# Main_Board_-_Single_v20.net
KiCad netlist of a schematic drawn in EAGLE
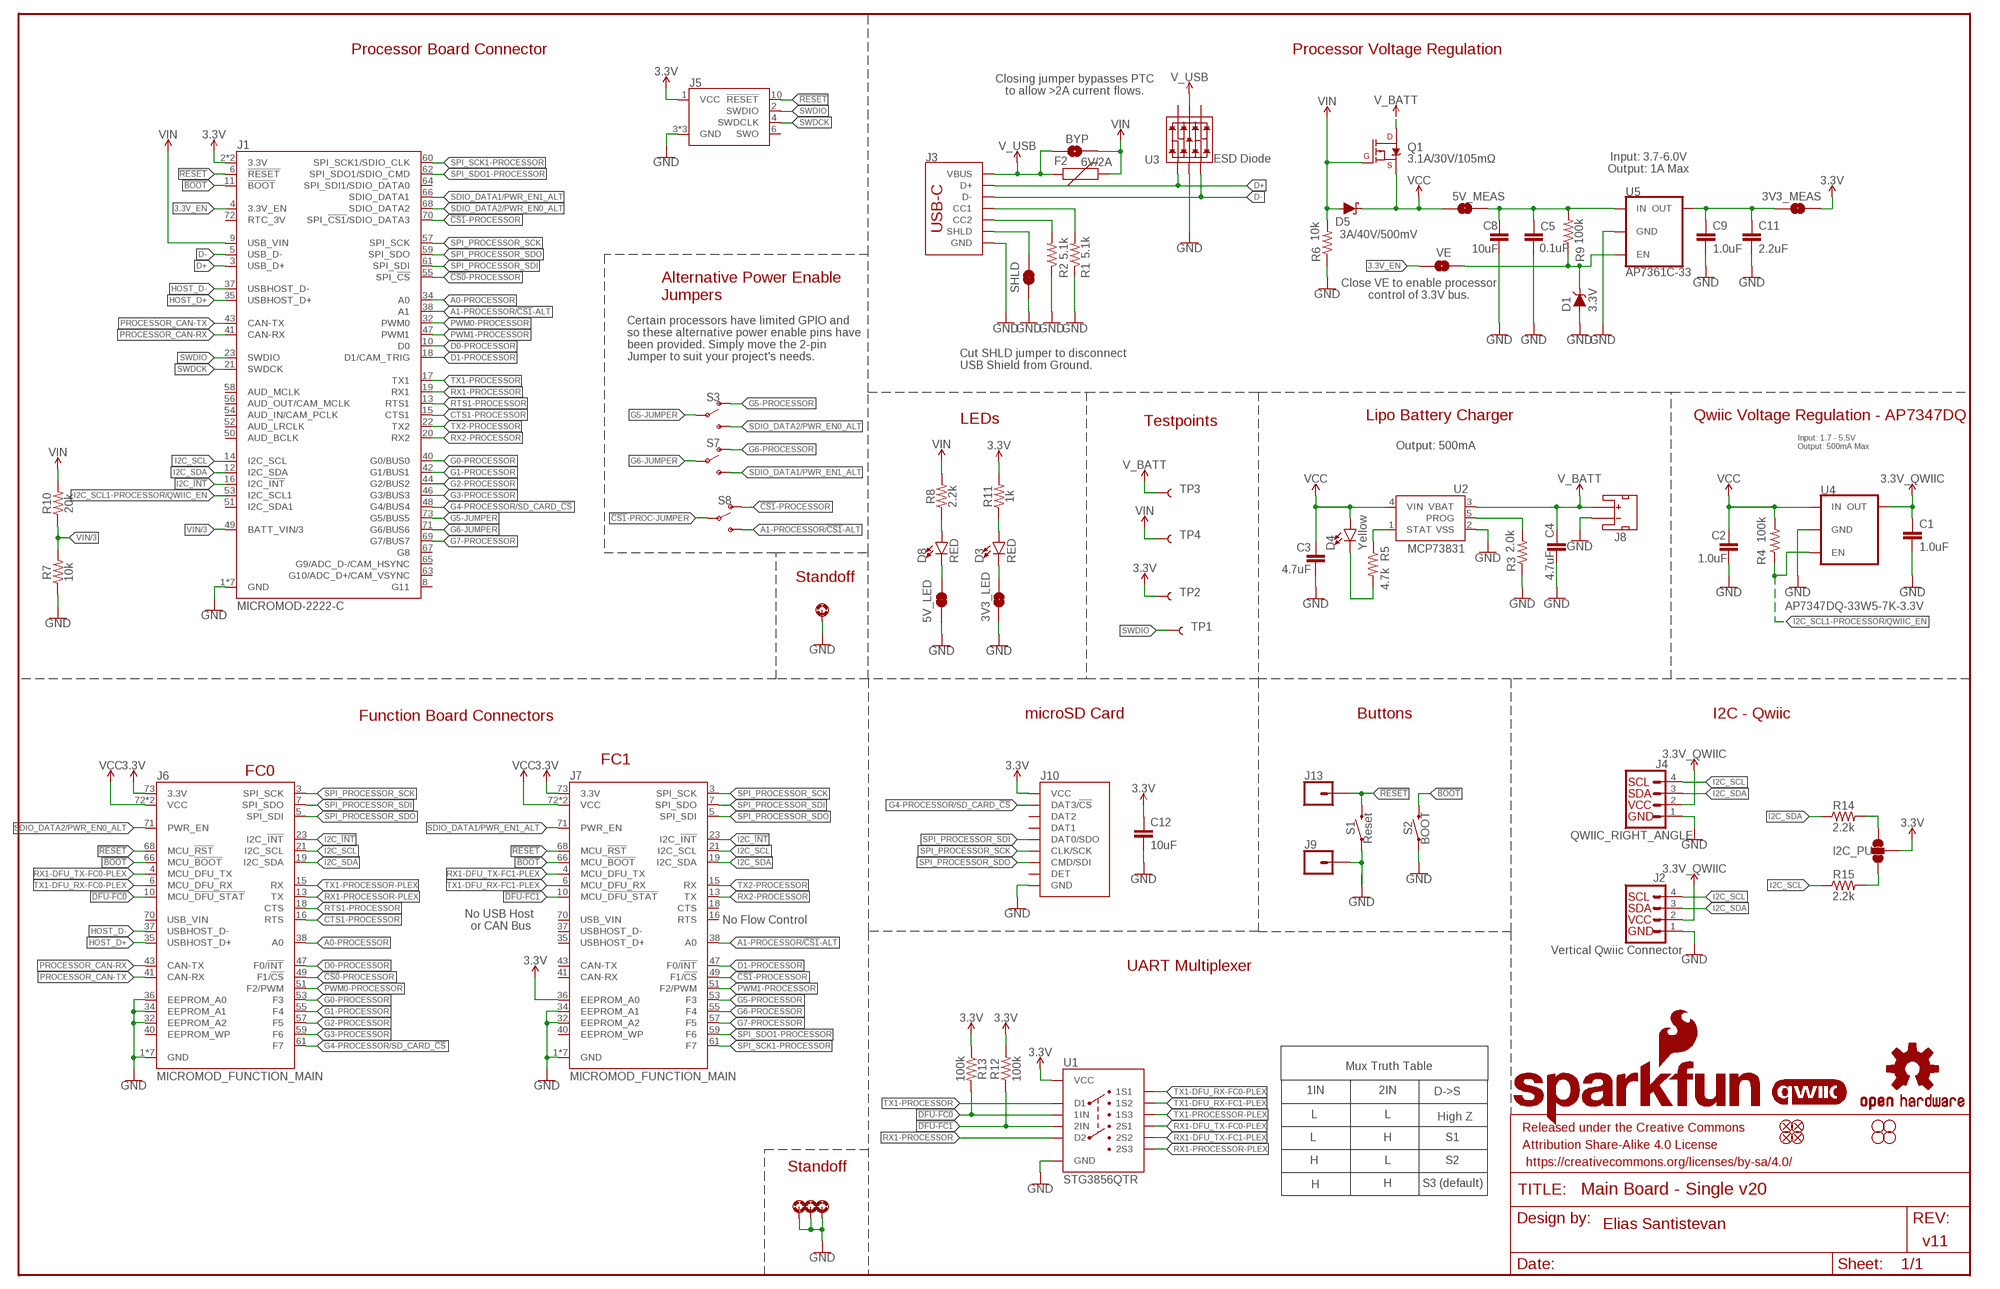
[diagram p0: schematic, sheet 1]

(export (version "E")
  (design (tool "Eeschema 10.0.6"))
  (components
    (comp (ref "3V3_LED")
      (value "JUMPER-SMT_2_NC_TRACE_SILK")
      (footprint "eagle-import:SMT-JUMPER_2_NC_TRACE_SILK")
      (libsource (lib "eagle-import") (part "JUMPER-SMT_2_NC_TRACE_SILK"))
    )
    (comp (ref "3V3_MEAS")
      (value "JUMPER-COMBO_2_NC_TRACE")
      (footprint "eagle-import:COMBO-JUMPER_2_NC_TRACE")
      (libsource (lib "eagle-import") (part "JUMPER-COMBO_2_NC_TRACE"))
    )
    (comp (ref "5V_LED")
      (value "JUMPER-SMT_2_NC_TRACE_SILK")
      (footprint "eagle-import:SMT-JUMPER_2_NC_TRACE_SILK")
      (libsource (lib "eagle-import") (part "JUMPER-SMT_2_NC_TRACE_SILK"))
    )
    (comp (ref "5V_MEAS")
      (value "JUMPER-COMBO_2_NC_TRACE")
      (footprint "eagle-import:COMBO-JUMPER_2_NC_TRACE")
      (libsource (lib "eagle-import") (part "JUMPER-COMBO_2_NC_TRACE"))
    )
    (comp (ref "BYP")
      (value "JUMPER-SMT_2_NO_SILK")
      (footprint "eagle-import:SMT-JUMPER_2_NO_SILK")
      (libsource (lib "eagle-import") (part "JUMPER-SMT_2_NO_SILK"))
    )
    (comp (ref "C1")
      (value "1.0uF")
      (footprint "eagle-import:0603")
      (libsource (lib "eagle-import") (part "1.0UF-0603-16V-10%"))
    )
    (comp (ref "C2")
      (value "1.0uF")
      (footprint "eagle-import:0603")
      (libsource (lib "eagle-import") (part "1.0UF-0603-16V-10%"))
    )
    (comp (ref "C3")
      (value "4.7uF")
      (footprint "eagle-import:0603")
      (libsource (lib "eagle-import") (part "4.7UF-0603-6.3V-(10%)"))
    )
    (comp (ref "C4")
      (value "4.7uF")
      (footprint "eagle-import:0603")
      (libsource (lib "eagle-import") (part "4.7UF-0603-35V-(20%)"))
    )
    (comp (ref "C5")
      (value "0.1uF")
      (footprint "eagle-import:0603")
      (libsource (lib "eagle-import") (part "0.1UF-0603-25V-(+80/-20%)"))
    )
    (comp (ref "C8")
      (value "10uF")
      (footprint "eagle-import:0805")
      (libsource (lib "eagle-import") (part "10UF-0805-10V-10%"))
    )
    (comp (ref "C9")
      (value "1.0uF")
      (footprint "eagle-import:0603")
      (libsource (lib "eagle-import") (part "1.0UF-0603-16V-10%"))
    )
    (comp (ref "C11")
      (value "2.2uF")
      (footprint "eagle-import:0603")
      (libsource (lib "eagle-import") (part "2.2UF-0603-10V-20%"))
    )
    (comp (ref "C12")
      (value "10uF")
      (footprint "eagle-import:0603")
      (libsource (lib "eagle-import") (part "10UF-0603-6.3V-20%"))
    )
    (comp (ref "D1")
      (value "3.3V")
      (footprint "eagle-import:SOD-323")
      (libsource (lib "eagle-import") (part "DIODE-ZENER-MM3Z3V3T1G"))
    )
    (comp (ref "D3")
      (value "RED")
      (footprint "eagle-import:LED-0603")
      (libsource (lib "eagle-import") (part "LED-RED0603"))
    )
    (comp (ref "D4")
      (value "Yellow")
      (footprint "eagle-import:LED-0603")
      (libsource (lib "eagle-import") (part "LED-YELLOW0603"))
    )
    (comp (ref "D5")
      (value "3A/40V/500mV")
      (footprint "eagle-import:SMA-DIODE")
      (libsource (lib "eagle-import") (part "DIODE-SCHOTTKY-B340A"))
    )
    (comp (ref "D8")
      (value "RED")
      (footprint "eagle-import:LED-0603")
      (libsource (lib "eagle-import") (part "LED-RED0603"))
    )
    (comp (ref "F2")
      (value "6V/2A")
      (footprint "eagle-import:1210")
      (libsource (lib "eagle-import") (part "PPTC_6V2A"))
    )
    (comp (ref "FD1")
      (value "FIDUCIAL1X2")
      (footprint "eagle-import:FIDUCIAL-1X2")
      (libsource (lib "eagle-import") (part "FIDUCIAL1X2"))
    )
    (comp (ref "FD2")
      (value "FIDUCIAL1X2")
      (footprint "eagle-import:FIDUCIAL-1X2")
      (libsource (lib "eagle-import") (part "FIDUCIAL1X2"))
    )
    (comp (ref "FD3")
      (value "FIDUCIAL1X2")
      (footprint "eagle-import:FIDUCIAL-1X2")
      (libsource (lib "eagle-import") (part "FIDUCIAL1X2"))
    )
    (comp (ref "FD4")
      (value "FIDUCIAL1X2")
      (footprint "eagle-import:FIDUCIAL-1X2")
      (libsource (lib "eagle-import") (part "FIDUCIAL1X2"))
    )
    (comp (ref "FRAME1")
      (value "FRAME-LEDGER")
      (footprint "eagle-import:CREATIVE_COMMONS")
      (libsource (lib "eagle-import") (part "FRAME-LEDGER"))
    )
    (comp (ref "H2")
      (value "STAND-OFF-REFLOW-M2.5_2.5MM_TALL")
      (footprint "eagle-import:STAND-OFF-REFLOW-M2.5")
      (libsource (lib "eagle-import") (part "STAND-OFF-REFLOW-M2.5_2.5MM_TALL"))
    )
    (comp (ref "H3")
      (value "STAND-OFF-REFLOW-M2.5_2.5MM_TALL")
      (footprint "eagle-import:STAND-OFF-REFLOW-M2.5")
      (libsource (lib "eagle-import") (part "STAND-OFF-REFLOW-M2.5_2.5MM_TALL"))
    )
    (comp (ref "H4")
      (value "STAND-OFF-REFLOW-M2.5_2.5MM_TALL")
      (footprint "eagle-import:STAND-OFF-REFLOW-M2.5")
      (libsource (lib "eagle-import") (part "STAND-OFF-REFLOW-M2.5_2.5MM_TALL"))
    )
    (comp (ref "H8")
      (value "STAND-OFF-REFLOW-M2.5_2.5MM_TALL")
      (footprint "eagle-import:STAND-OFF-REFLOW-M2.5")
      (libsource (lib "eagle-import") (part "STAND-OFF-REFLOW-M2.5_2.5MM_TALL"))
    )
    (comp (ref "H14")
      (value "STAND-OFFTIGHT")
      (footprint "eagle-import:STAND-OFF-TIGHT")
      (libsource (lib "eagle-import") (part "STAND-OFFTIGHT"))
    )
    (comp (ref "H15")
      (value "STAND-OFFTIGHT")
      (footprint "eagle-import:STAND-OFF-TIGHT")
      (libsource (lib "eagle-import") (part "STAND-OFFTIGHT"))
    )
    (comp (ref "H16")
      (value "STAND-OFFTIGHT")
      (footprint "eagle-import:STAND-OFF-TIGHT")
      (libsource (lib "eagle-import") (part "STAND-OFFTIGHT"))
    )
    (comp (ref "H17")
      (value "STAND-OFFTIGHT")
      (footprint "eagle-import:STAND-OFF-TIGHT")
      (libsource (lib "eagle-import") (part "STAND-OFFTIGHT"))
    )
    (comp (ref "I2C_PU")
      (value "JUMPER-SMT_3_2-NC_TRACE_SILK")
      (footprint "eagle-import:SMT-JUMPER_3_2-NC_TRACE_SILK")
      (libsource (lib "eagle-import") (part "JUMPER-SMT_3_2-NC_TRACE_SILK"))
    )
    (comp (ref "J1")
      (value "MICROMOD-2222-C")
      (footprint "eagle-import:M.2-CONNECTOR-E")
      (libsource (lib "eagle-import") (part "MICROMOD-2222-C"))
    )
    (comp (ref "J2")
      (value "Vertical Qwiic Connector")
      (footprint "eagle-import:JST04_1MM_VERT")
      (libsource (lib "eagle-import") (part "QWIIC_CONNECTOR"))
    )
    (comp (ref "J3")
      (value "USB_C_2-LAYER_PADS")
      (footprint "eagle-import:USB-C-16P-2LAYER-PADS")
      (libsource (lib "eagle-import") (part "USB_C_2-LAYER_PADS"))
    )
    (comp (ref "J4")
      (value "QWIIC_RIGHT_ANGLE")
      (footprint "eagle-import:JST04_1MM_RA")
      (libsource (lib "eagle-import") (part "QWIIC_CONNECTORJS-1MM"))
    )
    (comp (ref "J5")
      (value "CORTEX_JTAG_DEBUG_MINIMUM_PTH")
      (footprint "eagle-import:2X5-PTH-1.27MM")
      (libsource (lib "eagle-import") (part "CORTEX_JTAG_DEBUG_MINIMUM_PTH"))
    )
    (comp (ref "J6")
      (value "MICROMOD_FUNCTION_MAIN")
      (footprint "eagle-import:M.2-CONNECTOR-E-FUNCTION-STANDARD")
      (libsource (lib "eagle-import") (part "MICROMOD_FUNCTION_MAIN"))
    )
    (comp (ref "J7")
      (value "MICROMOD_FUNCTION_MAIN")
      (footprint "eagle-import:M.2-CONNECTOR-E-FUNCTION-STANDARD")
      (libsource (lib "eagle-import") (part "MICROMOD_FUNCTION_MAIN"))
    )
    (comp (ref "J8")
      (value "JST_2MM_MALE")
      (footprint "eagle-import:JST-2-SMD")
      (libsource (lib "eagle-import") (part "JST_2MM_MALE"))
    )
    (comp (ref "J9")
      (value "CONN_01PTH_NO_SILK_YES_STOP")
      (footprint "eagle-import:1X01_NO_SILK")
      (libsource (lib "eagle-import") (part "CONN_01PTH_NO_SILK_YES_STOP"))
    )
    (comp (ref "J10")
      (value "MICRO-SD-PUSH-PUSH-EXT-PIN")
      (footprint "eagle-import:MICROSD-EXTERNALPIN")
      (libsource (lib "eagle-import") (part "MICRO-SD-PUSH-PUSH-EXT-PIN"))
    )
    (comp (ref "J13")
      (value "CONN_01PTH_NO_SILK_YES_STOP")
      (footprint "eagle-import:1X01_NO_SILK")
      (libsource (lib "eagle-import") (part "CONN_01PTH_NO_SILK_YES_STOP"))
    )
    (comp (ref "LOGO1")
      (value "QWIIC_LOGO_8MM")
      (footprint "eagle-import:QWIIC_8MM")
      (libsource (lib "eagle-import") (part "QWIIC_LOGO_8MM"))
    )
    (comp (ref "LOGO2")
      (value "SFE_LOGO_NAME_FLAME.3_INCH")
      (footprint "eagle-import:SFE_LOGO_NAME_FLAME_.3")
      (libsource (lib "eagle-import") (part "SFE_LOGO_NAME_FLAME.3_INCH"))
    )
    (comp (ref "LOGO3")
      (value "OSHW-LOGOL")
      (footprint "eagle-import:OSHW-LOGO-L")
      (libsource (lib "eagle-import") (part "OSHW-LOGOL"))
    )
    (comp (ref "Q1")
      (value "3.1A/30V/105mΩ")
      (footprint "eagle-import:SOT23-3")
      (libsource (lib "eagle-import") (part "MOSFET_PCH-DMG2307L"))
    )
    (comp (ref "R1")
      (value "5.1k")
      (footprint "eagle-import:0603")
      (libsource (lib "eagle-import") (part "5.1KOHM5.1KOHM-0603-1/10W-1%"))
    )
    (comp (ref "R2")
      (value "5.1k")
      (footprint "eagle-import:0603")
      (libsource (lib "eagle-import") (part "5.1KOHM5.1KOHM-0603-1/10W-1%"))
    )
    (comp (ref "R3")
      (value "2.0k")
      (footprint "eagle-import:0603")
      (libsource (lib "eagle-import") (part "2.0KOHM-0603-1/10W-5%"))
    )
    (comp (ref "R4")
      (value "100k")
      (footprint "eagle-import:0603")
      (libsource (lib "eagle-import") (part "100KOHM-0603-1/10W-1%"))
    )
    (comp (ref "R5")
      (value "4.7k")
      (footprint "eagle-import:0603")
      (libsource (lib "eagle-import") (part "4.7KOHM-0603-1/10W-1%"))
    )
    (comp (ref "R6")
      (value "10k")
      (footprint "eagle-import:0603")
      (libsource (lib "eagle-import") (part "10KOHM-0603-1/10W-1%"))
    )
    (comp (ref "R7")
      (value "10k")
      (footprint "eagle-import:0603")
      (libsource (lib "eagle-import") (part "10KOHM-0603-1/10W-1%"))
    )
    (comp (ref "R8")
      (value "2.2k")
      (footprint "eagle-import:0603")
      (libsource (lib "eagle-import") (part "2.2KOHM-0603-1/10W-1%"))
    )
    (comp (ref "R9")
      (value "100k")
      (footprint "eagle-import:0603")
      (libsource (lib "eagle-import") (part "100KOHM-0603-1/10W-1%"))
    )
    (comp (ref "R10")
      (value "20k")
      (footprint "eagle-import:0603")
      (libsource (lib "eagle-import") (part "20KOHM-0603-1/10W-1%"))
    )
    (comp (ref "R11")
      (value "1k")
      (footprint "eagle-import:0603")
      (libsource (lib "eagle-import") (part "1KOHM-0603-1/10W-1%"))
    )
    (comp (ref "R12")
      (value "100k")
      (footprint "eagle-import:0603")
      (libsource (lib "eagle-import") (part "100KOHM-0603-1/10W-1%"))
    )
    (comp (ref "R13")
      (value "100k")
      (footprint "eagle-import:0603")
      (libsource (lib "eagle-import") (part "100KOHM-0603-1/10W-1%"))
    )
    (comp (ref "R14")
      (value "2.2k")
      (footprint "eagle-import:0603")
      (libsource (lib "eagle-import") (part "2.2KOHM-0603-1/10W-1%"))
    )
    (comp (ref "R15")
      (value "2.2k")
      (footprint "eagle-import:0603")
      (libsource (lib "eagle-import") (part "2.2KOHM-0603-1/10W-1%"))
    )
    (comp (ref "S1")
      (value "Reset")
      (footprint "eagle-import:TACTILE_SWITCH_SMD_5.2MM")
      (libsource (lib "eagle-import") (part "MOMENTARY-SWITCH-SPST-SMD-5.2-TALL-REDUNDANT"))
    )
    (comp (ref "S2")
      (value "BOOT")
      (footprint "eagle-import:TACTILE_SWITCH_SMD_5.2MM")
      (libsource (lib "eagle-import") (part "MOMENTARY-SWITCH-SPST-SMD-5.2-TALL-REDUNDANT"))
    )
    (comp (ref "S3")
      (value "SWITCH-SPDT-SMD-RIGHT-ANGLE")
      (footprint "eagle-import:SWITCH_SPST_SMD_A")
      (libsource (lib "eagle-import") (part "SWITCH-SPDT-SMD-RIGHT-ANGLE"))
    )
    (comp (ref "S7")
      (value "SWITCH-SPDT-SMD-RIGHT-ANGLE")
      (footprint "eagle-import:SWITCH_SPST_SMD_A")
      (libsource (lib "eagle-import") (part "SWITCH-SPDT-SMD-RIGHT-ANGLE"))
    )
    (comp (ref "S8")
      (value "SWITCH-SPDT-SMD-RIGHT-ANGLE")
      (footprint "eagle-import:SWITCH_SPST_SMD_A")
      (libsource (lib "eagle-import") (part "SWITCH-SPDT-SMD-RIGHT-ANGLE"))
    )
    (comp (ref "SHLD")
      (value "JUMPER-SMT_2_NC_TRACE_SILK")
      (footprint "eagle-import:SMT-JUMPER_2_NC_TRACE_SILK")
      (libsource (lib "eagle-import") (part "JUMPER-SMT_2_NC_TRACE_SILK"))
    )
    (comp (ref "TP1")
      (value "TEST-POINT3X5")
      (footprint "eagle-import:PAD.03X.05")
      (libsource (lib "eagle-import") (part "TEST-POINT3X5"))
    )
    (comp (ref "TP2")
      (value "TEST-POINT3X5")
      (footprint "eagle-import:PAD.03X.05")
      (libsource (lib "eagle-import") (part "TEST-POINT3X5"))
    )
    (comp (ref "TP3")
      (value "TEST-POINT3X5")
      (footprint "eagle-import:PAD.03X.05")
      (libsource (lib "eagle-import") (part "TEST-POINT3X5"))
    )
    (comp (ref "TP4")
      (value "TEST-POINT3X5")
      (footprint "eagle-import:PAD.03X.05")
      (libsource (lib "eagle-import") (part "TEST-POINT3X5"))
    )
    (comp (ref "U1")
      (value "STG3856QTR")
      (footprint "eagle-import:STG3856")
      (libsource (lib "eagle-import") (part "STG3856QTR"))
    )
    (comp (ref "U2")
      (value "MCP73831")
      (footprint "eagle-import:SOT23-5")
      (libsource (lib "eagle-import") (part "MCP73831"))
    )
    (comp (ref "U3")
      (value "ESD Diode")
      (footprint "eagle-import:SOT-23-6")
      (libsource (lib "eagle-import") (part "TVS_DIODE_ARRAYSMD"))
    )
    (comp (ref "U4")
      (value "AP7347DQ-33W5-7K-3.3V")
      (footprint "eagle-import:SOT25")
      (libsource (lib "eagle-import") (part "AP7347DQ-33W5-7K-3.3V"))
    )
    (comp (ref "U5")
      (value "AP7361C-33")
      (footprint "eagle-import:UDFN-8")
      (libsource (lib "eagle-import") (part "AP7361C-33FGEUDFN-8"))
    )
    (comp (ref "VE")
      (value "JUMPER-SMT_2_NO_SILK")
      (footprint "eagle-import:SMT-JUMPER_2_NO_SILK")
      (libsource (lib "eagle-import") (part "JUMPER-SMT_2_NO_SILK"))
    )
  )
  (nets
    (net (code "1") (name "/A1-PROCESSOR{slash}~{CS1}-ALT") (class "Default")
      (node (ref "J1") (pin "38") (pinfunction "A1_38") (pintype "bidirectional"))
      (node (ref "J7") (pin "38") (pinfunction "A0_38") (pintype "bidirectional"))
      (node (ref "S8") (pin "3") (pinfunction "S_3") (pintype "passive"))
    )
    (net (code "2") (name "/G4-PROCESSOR{slash}SD_CARD_~{CS}") (class "Default")
      (node (ref "J1") (pin "48") (pinfunction "G4/BUS4_48") (pintype "bidirectional"))
      (node (ref "J10") (pin "2") (pinfunction "DAT3/~{CS}_2") (pintype "bidirectional"))
      (node (ref "J6") (pin "61") (pinfunction "F7_61") (pintype "bidirectional"))
    )
    (net (code "3") (name "/I2C_~{INT}") (class "Default")
      (node (ref "J1") (pin "16") (pinfunction "I2C_~{INT}_16") (pintype "bidirectional"))
      (node (ref "J6") (pin "23") (pinfunction "I2C_~{INT}_23") (pintype "bidirectional"))
      (node (ref "J7") (pin "23") (pinfunction "I2C_~{INT}_23") (pintype "bidirectional"))
    )
    (net (code "4") (name "/~{BOOT}") (class "Default")
      (node (ref "J1") (pin "11") (pinfunction "~{BOOT}_11") (pintype "bidirectional"))
      (node (ref "J6") (pin "66") (pinfunction "MCU_~{BOOT}_66") (pintype "bidirectional"))
      (node (ref "J7") (pin "66") (pinfunction "MCU_~{BOOT}_66") (pintype "bidirectional"))
      (node (ref "S2") (pin "3") (pinfunction "2_3") (pintype "passive"))
      (node (ref "S2") (pin "4") (pinfunction "2_4") (pintype "passive"))
    )
    (net (code "5") (name "/~{CS0}-PROCESSOR") (class "Default")
      (node (ref "J1") (pin "55") (pinfunction "SPI_~{CS}_55") (pintype "bidirectional"))
      (node (ref "J6") (pin "49") (pinfunction "F1/~{CS}_49") (pintype "bidirectional"))
    )
    (net (code "6") (name "/~{CS1}-PROC-JUMPER") (class "Default")
      (node (ref "S8") (pin "2") (pinfunction "P_2") (pintype "passive"))
    )
    (net (code "7") (name "/~{CS1}-PROCESSOR") (class "Default")
      (node (ref "J1") (pin "70") (pinfunction "SPI_~{CS1}/SDIO_DATA3_70") (pintype "bidirectional"))
      (node (ref "J7") (pin "49") (pinfunction "F1/~{CS}_49") (pintype "bidirectional"))
      (node (ref "S8") (pin "1") (pinfunction "O_1") (pintype "passive"))
    )
    (net (code "8") (name "/~{DFU-FC0}") (class "Default")
      (node (ref "J6") (pin "10") (pinfunction "MCU_~{DFU_STAT}_10") (pintype "bidirectional"))
      (node (ref "R13") (pin "2") (pinfunction "2_2") (pintype "passive"))
      (node (ref "U1") (pin "P12") (pinfunction "1IN_P12") (pintype "bidirectional"))
    )
    (net (code "9") (name "/~{DFU-FC1}") (class "Default")
      (node (ref "J7") (pin "10") (pinfunction "MCU_~{DFU_STAT}_10") (pintype "bidirectional"))
      (node (ref "R12") (pin "1") (pinfunction "1_1") (pintype "passive"))
      (node (ref "U1") (pin "P10") (pinfunction "2IN_P10") (pintype "bidirectional"))
    )
    (net (code "10") (name "/~{RESET}") (class "Default")
      (node (ref "J1") (pin "6") (pinfunction "~{RESET}_6") (pintype "bidirectional"))
      (node (ref "J13") (pin "1") (pinfunction "1_1") (pintype "passive"))
      (node (ref "J5") (pin "10") (pinfunction "~{RESET}_10") (pintype "bidirectional"))
      (node (ref "J6") (pin "68") (pinfunction "MCU_~{RST}_68") (pintype "bidirectional"))
      (node (ref "J7") (pin "68") (pinfunction "MCU_~{RST}_68") (pintype "bidirectional"))
      (node (ref "S1") (pin "3") (pinfunction "2_3") (pintype "passive"))
      (node (ref "S1") (pin "4") (pinfunction "2_4") (pintype "passive"))
    )
    (net (code "11") (name "3.3V") (class "Default")
      (node (ref "3V3_MEAS") (pin "2") (pinfunction "2_2") (pintype "passive"))
      (node (ref "3V3_MEAS") (pin "4") (pinfunction "2_4") (pintype "passive"))
      (node (ref "C12") (pin "1") (pinfunction "1_1") (pintype "passive"))
      (node (ref "I2C_PU") (pin "2") (pinfunction "2_2") (pintype "passive"))
      (node (ref "J1") (pin "2") (pinfunction "3.3V_2") (pintype "bidirectional"))
      (node (ref "J1") (pin "74") (pinfunction "3.3V_74") (pintype "bidirectional"))
      (node (ref "J10") (pin "4") (pinfunction "VCC_4") (pintype "bidirectional"))
      (node (ref "J5") (pin "1") (pinfunction "VCC_1") (pintype "bidirectional"))
      (node (ref "J6") (pin "73") (pinfunction "3.3V_73") (pintype "bidirectional"))
      (node (ref "J7") (pin "36") (pinfunction "EEPROM_A0_36") (pintype "bidirectional"))
      (node (ref "J7") (pin "73") (pinfunction "3.3V_73") (pintype "bidirectional"))
      (node (ref "R11") (pin "2") (pinfunction "2_2") (pintype "passive"))
      (node (ref "R12") (pin "2") (pinfunction "2_2") (pintype "passive"))
      (node (ref "R13") (pin "1") (pinfunction "1_1") (pintype "passive"))
      (node (ref "TP2") (pin "1") (pinfunction "1_1") (pintype "bidirectional"))
      (node (ref "U1") (pin "P11") (pinfunction "VCC_P11") (pintype "power_in"))
    )
    (net (code "12") (name "3.3V_EN") (class "Default")
      (node (ref "J1") (pin "4") (pinfunction "3.3V_EN_4") (pintype "bidirectional"))
      (node (ref "VE") (pin "1") (pinfunction "1_1") (pintype "passive"))
    )
    (net (code "13") (name "3.3V_QWIIC") (class "Default")
      (node (ref "C1") (pin "1") (pinfunction "1_1") (pintype "passive"))
      (node (ref "J2") (pin "2") (pinfunction "2_2") (pintype "power_in"))
      (node (ref "J4") (pin "2") (pinfunction "2_2") (pintype "power_in"))
      (node (ref "U4") (pin "5") (pinfunction "OUT_5") (pintype "passive"))
    )
    (net (code "14") (name "A0-PROCESSOR") (class "Default")
      (node (ref "J1") (pin "34") (pinfunction "A0_34") (pintype "bidirectional"))
      (node (ref "J6") (pin "38") (pinfunction "A0_38") (pintype "bidirectional"))
    )
    (net (code "15") (name "CTS1-PROCESSOR") (class "Default")
      (node (ref "J1") (pin "15") (pinfunction "CTS1_15") (pintype "bidirectional"))
      (node (ref "J6") (pin "16") (pinfunction "RTS_16") (pintype "bidirectional"))
    )
    (net (code "16") (name "D+") (class "Default")
      (node (ref "J1") (pin "3") (pinfunction "USB_D+_3") (pintype "bidirectional"))
      (node (ref "J3") (pin "A6") (pinfunction "D+_A6") (pintype "bidirectional"))
      (node (ref "J3") (pin "B6") (pinfunction "D+_B6") (pintype "bidirectional"))
      (node (ref "U3") (pin "1") (pinfunction "IO1_1") (pintype "bidirectional"))
    )
    (net (code "17") (name "D-") (class "Default")
      (node (ref "J1") (pin "5") (pinfunction "USB_D-_5") (pintype "bidirectional"))
      (node (ref "J3") (pin "A7") (pinfunction "D-_A7") (pintype "bidirectional"))
      (node (ref "J3") (pin "B7") (pinfunction "D-_B7") (pintype "bidirectional"))
      (node (ref "U3") (pin "3") (pinfunction "IO2_3") (pintype "bidirectional"))
    )
    (net (code "18") (name "D0-PROCESSOR") (class "Default")
      (node (ref "J1") (pin "10") (pinfunction "D0_10") (pintype "bidirectional"))
      (node (ref "J6") (pin "47") (pinfunction "F0/~{INT}_47") (pintype "bidirectional"))
    )
    (net (code "19") (name "D1-PROCESSOR") (class "Default")
      (node (ref "J1") (pin "18") (pinfunction "D1/CAM_TRIG_18") (pintype "bidirectional"))
      (node (ref "J7") (pin "47") (pinfunction "F0/~{INT}_47") (pintype "bidirectional"))
    )
    (net (code "20") (name "G0-PROCESSOR") (class "Default")
      (node (ref "J1") (pin "40") (pinfunction "G0/BUS0_40") (pintype "bidirectional"))
      (node (ref "J6") (pin "53") (pinfunction "F3_53") (pintype "bidirectional"))
    )
    (net (code "21") (name "G1-PROCESSOR") (class "Default")
      (node (ref "J1") (pin "42") (pinfunction "G1/BUS1_42") (pintype "bidirectional"))
      (node (ref "J6") (pin "55") (pinfunction "F4_55") (pintype "bidirectional"))
    )
    (net (code "22") (name "G2-PROCESSOR") (class "Default")
      (node (ref "J1") (pin "44") (pinfunction "G2/BUS2_44") (pintype "bidirectional"))
      (node (ref "J6") (pin "57") (pinfunction "F5_57") (pintype "bidirectional"))
    )
    (net (code "23") (name "G3-PROCESSOR") (class "Default")
      (node (ref "J1") (pin "46") (pinfunction "G3/BUS3_46") (pintype "bidirectional"))
      (node (ref "J6") (pin "59") (pinfunction "F6_59") (pintype "bidirectional"))
    )
    (net (code "24") (name "G5-JUMPER") (class "Default")
      (node (ref "J1") (pin "73") (pinfunction "G5/BUS5_73") (pintype "bidirectional"))
      (node (ref "S3") (pin "2") (pinfunction "P_2") (pintype "passive"))
    )
    (net (code "25") (name "G5-PROCESSOR") (class "Default")
      (node (ref "J7") (pin "53") (pinfunction "F3_53") (pintype "bidirectional"))
      (node (ref "S3") (pin "1") (pinfunction "O_1") (pintype "passive"))
    )
    (net (code "26") (name "G6-JUMPER") (class "Default")
      (node (ref "J1") (pin "71") (pinfunction "G6/BUS6_71") (pintype "bidirectional"))
      (node (ref "S7") (pin "2") (pinfunction "P_2") (pintype "passive"))
    )
    (net (code "27") (name "G6-PROCESSOR") (class "Default")
      (node (ref "J7") (pin "55") (pinfunction "F4_55") (pintype "bidirectional"))
      (node (ref "S7") (pin "1") (pinfunction "O_1") (pintype "passive"))
    )
    (net (code "28") (name "G7-PROCESSOR") (class "Default")
      (node (ref "J1") (pin "69") (pinfunction "G7/BUS7_69") (pintype "bidirectional"))
      (node (ref "J7") (pin "57") (pinfunction "F5_57") (pintype "bidirectional"))
    )
    (net (code "29") (name "GND") (class "Default")
      (node (ref "3V3_LED") (pin "1") (pinfunction "1_1") (pintype "passive"))
      (node (ref "5V_LED") (pin "1") (pinfunction "1_1") (pintype "passive"))
      (node (ref "C1") (pin "2") (pinfunction "2_2") (pintype "passive"))
      (node (ref "C11") (pin "2") (pinfunction "2_2") (pintype "passive"))
      (node (ref "C12") (pin "2") (pinfunction "2_2") (pintype "passive"))
      (node (ref "C2") (pin "2") (pinfunction "2_2") (pintype "passive"))
      (node (ref "C3") (pin "2") (pinfunction "2_2") (pintype "passive"))
      (node (ref "C4") (pin "2") (pinfunction "2_2") (pintype "passive"))
      (node (ref "C5") (pin "2") (pinfunction "2_2") (pintype "passive"))
      (node (ref "C8") (pin "2") (pinfunction "2_2") (pintype "passive"))
      (node (ref "C9") (pin "2") (pinfunction "2_2") (pintype "passive"))
      (node (ref "D1") (pin "A") (pinfunction "A_A") (pintype "passive"))
      (node (ref "H2") (pin "1") (pinfunction "1_1") (pintype "bidirectional"))
      (node (ref "H3") (pin "1") (pinfunction "1_1") (pintype "bidirectional"))
      (node (ref "H4") (pin "1") (pinfunction "1_1") (pintype "bidirectional"))
      (node (ref "H8") (pin "1") (pinfunction "1_1") (pintype "bidirectional"))
      (node (ref "J1") (pin "1") (pinfunction "GND_1") (pintype "bidirectional"))
      (node (ref "J1") (pin "33") (pinfunction "GND_33") (pintype "bidirectional"))
      (node (ref "J1") (pin "36") (pinfunction "GND_36") (pintype "bidirectional"))
      (node (ref "J1") (pin "39") (pinfunction "GND_39") (pintype "bidirectional"))
      (node (ref "J1") (pin "45") (pinfunction "GND_45") (pintype "bidirectional"))
      (node (ref "J1") (pin "7") (pinfunction "GND_7") (pintype "bidirectional"))
      (node (ref "J1") (pin "75") (pinfunction "GND_75") (pintype "bidirectional"))
      (node (ref "J10") (pin "10") (pinfunction "GND_10") (pintype "bidirectional"))
      (node (ref "J10") (pin "11") (pinfunction "GND_11") (pintype "bidirectional"))
      (node (ref "J10") (pin "12") (pinfunction "GND_12") (pintype "bidirectional"))
      (node (ref "J10") (pin "13") (pinfunction "GND_13") (pintype "bidirectional"))
      (node (ref "J10") (pin "6") (pinfunction "GND_6") (pintype "bidirectional"))
      (node (ref "J2") (pin "1") (pinfunction "1_1") (pintype "power_in"))
      (node (ref "J3") (pin "GND") (pinfunction "GND_GND") (pintype "bidirectional"))
      (node (ref "J3") (pin "GND2") (pinfunction "GND_GND2") (pintype "bidirectional"))
      (node (ref "J4") (pin "1") (pinfunction "1_1") (pintype "power_in"))
      (node (ref "J5") (pin "3") (pinfunction "GND_3") (pintype "bidirectional"))
      (node (ref "J5") (pin "5") (pinfunction "GND_5") (pintype "bidirectional"))
      (node (ref "J5") (pin "9") (pinfunction "GND_9") (pintype "bidirectional"))
      (node (ref "J6") (pin "1") (pinfunction "GND_1") (pintype "bidirectional"))
      (node (ref "J6") (pin "2") (pinfunction "GND_2") (pintype "bidirectional"))
      (node (ref "J6") (pin "32") (pinfunction "EEPROM_A2_32") (pintype "bidirectional"))
      (node (ref "J6") (pin "33") (pinfunction "GND_33") (pintype "bidirectional"))
      (node (ref "J6") (pin "34") (pinfunction "EEPROM_A1_34") (pintype "bidirectional"))
      (node (ref "J6") (pin "36") (pinfunction "EEPROM_A0_36") (pintype "bidirectional"))
      (node (ref "J6") (pin "39") (pinfunction "GND_39") (pintype "bidirectional"))
      (node (ref "J6") (pin "45") (pinfunction "GND_45") (pintype "bidirectional"))
      (node (ref "J6") (pin "75") (pinfunction "GND_75") (pintype "bidirectional"))
      (node (ref "J6") (pin "8") (pinfunction "GND_8") (pintype "bidirectional"))
      (node (ref "J7") (pin "1") (pinfunction "GND_1") (pintype "bidirectional"))
      (node (ref "J7") (pin "2") (pinfunction "GND_2") (pintype "bidirectional"))
      (node (ref "J7") (pin "32") (pinfunction "EEPROM_A2_32") (pintype "bidirectional"))
      (node (ref "J7") (pin "33") (pinfunction "GND_33") (pintype "bidirectional"))
      (node (ref "J7") (pin "34") (pinfunction "EEPROM_A1_34") (pintype "bidirectional"))
      (node (ref "J7") (pin "39") (pinfunction "GND_39") (pintype "bidirectional"))
      (node (ref "J7") (pin "45") (pinfunction "GND_45") (pintype "bidirectional"))
      (node (ref "J7") (pin "75") (pinfunction "GND_75") (pintype "bidirectional"))
      (node (ref "J7") (pin "8") (pinfunction "GND_8") (pintype "bidirectional"))
      (node (ref "J8") (pin "1") (pinfunction "-_1") (pintype "bidirectional"))
      (node (ref "J9") (pin "1") (pinfunction "1_1") (pintype "passive"))
      (node (ref "R1") (pin "1") (pinfunction "1_1") (pintype "passive"))
      (node (ref "R2") (pin "1") (pinfunction "1_1") (pintype "passive"))
      (node (ref "R3") (pin "1") (pinfunction "1_1") (pintype "passive"))
      (node (ref "R6") (pin "1") (pinfunction "1_1") (pintype "passive"))
      (node (ref "R7") (pin "1") (pinfunction "1_1") (pintype "passive"))
      (node (ref "S1") (pin "1") (pinfunction "1_1") (pintype "passive"))
      (node (ref "S1") (pin "2") (pinfunction "1_2") (pintype "passive"))
      (node (ref "S2") (pin "1") (pinfunction "1_1") (pintype "passive"))
      (node (ref "S2") (pin "2") (pinfunction "1_2") (pintype "passive"))
      (node (ref "SHLD") (pin "1") (pinfunction "1_1") (pintype "passive"))
      (node (ref "U1") (pin "P5") (pinfunction "GND_P5") (pintype "power_in"))
      (node (ref "U2") (pin "2") (pinfunction "VSS_2") (pintype "power_in"))
      (node (ref "U3") (pin "2") (pinfunction "VSS_2") (pintype "bidirectional"))
      (node (ref "U4") (pin "2") (pinfunction "GND_2") (pintype "input"))
      (node (ref "U5") (pin "4") (pinfunction "GND_4") (pintype "input"))
      (node (ref "U5") (pin "EP") (pinfunction "GND_EP") (pintype "input"))
    )
    (net (code "30") (name "HOST_D+") (class "Default")
      (node (ref "J1") (pin "35") (pinfunction "USBHOST_D+_35") (pintype "bidirectional"))
      (node (ref "J6") (pin "35") (pinfunction "USBHOST_D+_35") (pintype "bidirectional"))
    )
    (net (code "31") (name "HOST_D-") (class "Default")
      (node (ref "J1") (pin "37") (pinfunction "USBHOST_D-_37") (pintype "bidirectional"))
      (node (ref "J6") (pin "37") (pinfunction "USBHOST_D-_37") (pintype "bidirectional"))
    )
    (net (code "32") (name "I2C_SCL") (class "Default")
      (node (ref "J1") (pin "14") (pinfunction "I2C_SCL_14") (pintype "bidirectional"))
      (node (ref "J2") (pin "4") (pinfunction "4_4") (pintype "passive"))
      (node (ref "J4") (pin "4") (pinfunction "4_4") (pintype "passive"))
      (node (ref "J6") (pin "21") (pinfunction "I2C_SCL_21") (pintype "bidirectional"))
      (node (ref "J7") (pin "21") (pinfunction "I2C_SCL_21") (pintype "bidirectional"))
      (node (ref "R15") (pin "1") (pinfunction "1_1") (pintype "passive"))
    )
    (net (code "33") (name "I2C_SCL1-PROCESSOR{slash}QWIIC_EN") (class "Default")
      (node (ref "J1") (pin "53") (pinfunction "I2C_SCL1_53") (pintype "bidirectional"))
      (node (ref "R4") (pin "1") (pinfunction "1_1") (pintype "passive"))
      (node (ref "U4") (pin "3") (pinfunction "EN_3") (pintype "input"))
    )
    (net (code "34") (name "I2C_SDA") (class "Default")
      (node (ref "J1") (pin "12") (pinfunction "I2C_SDA_12") (pintype "bidirectional"))
      (node (ref "J2") (pin "3") (pinfunction "3_3") (pintype "passive"))
      (node (ref "J4") (pin "3") (pinfunction "3_3") (pintype "passive"))
      (node (ref "J6") (pin "19") (pinfunction "I2C_SDA_19") (pintype "bidirectional"))
      (node (ref "J7") (pin "19") (pinfunction "I2C_SDA_19") (pintype "bidirectional"))
      (node (ref "R14") (pin "1") (pinfunction "1_1") (pintype "passive"))
    )
    (net (code "35") (name "Net-(3V3_LED-Pad2)") (class "Default")
      (node (ref "3V3_LED") (pin "2") (pinfunction "2_2") (pintype "passive"))
      (node (ref "D3") (pin "C") (pinfunction "C_C") (pintype "passive"))
    )
    (net (code "36") (name "Net-(5V_LED-Pad2)") (class "Default")
      (node (ref "5V_LED") (pin "2") (pinfunction "2_2") (pintype "passive"))
      (node (ref "D8") (pin "C") (pinfunction "C_C") (pintype "passive"))
    )
    (net (code "37") (name "Net-(D3-PadA)") (class "Default")
      (node (ref "D3") (pin "A") (pinfunction "A_A") (pintype "passive"))
      (node (ref "R11") (pin "1") (pinfunction "1_1") (pintype "passive"))
    )
    (net (code "38") (name "Net-(D4-PadC)") (class "Default")
      (node (ref "D4") (pin "C") (pinfunction "C_C") (pintype "passive"))
      (node (ref "R5") (pin "2") (pinfunction "2_2") (pintype "passive"))
    )
    (net (code "39") (name "Net-(D8-PadA)") (class "Default")
      (node (ref "D8") (pin "A") (pinfunction "A_A") (pintype "passive"))
      (node (ref "R8") (pin "1") (pinfunction "1_1") (pintype "passive"))
    )
    (net (code "40") (name "Net-(I2C_PU-Pad1)") (class "Default")
      (node (ref "I2C_PU") (pin "1") (pinfunction "1_1") (pintype "passive"))
      (node (ref "R15") (pin "2") (pinfunction "2_2") (pintype "passive"))
    )
    (net (code "41") (name "Net-(I2C_PU-Pad3)") (class "Default")
      (node (ref "I2C_PU") (pin "3") (pinfunction "3_3") (pintype "passive"))
      (node (ref "R14") (pin "2") (pinfunction "2_2") (pintype "passive"))
    )
    (net (code "42") (name "Net-(J3-CC1)") (class "Default")
      (node (ref "J3") (pin "A5") (pinfunction "CC1_A5") (pintype "bidirectional"))
      (node (ref "R1") (pin "2") (pinfunction "2_2") (pintype "passive"))
    )
    (net (code "43") (name "Net-(J3-CC2)") (class "Default")
      (node (ref "J3") (pin "B5") (pinfunction "CC2_B5") (pintype "bidirectional"))
      (node (ref "R2") (pin "2") (pinfunction "2_2") (pintype "passive"))
    )
    (net (code "44") (name "Net-(J3-SHLD-PadSHLD1)") (class "Default")
      (node (ref "J3") (pin "SHLD1") (pinfunction "SHLD_SHLD1") (pintype "bidirectional"))
      (node (ref "J3") (pin "SHLD2") (pinfunction "SHLD_SHLD2") (pintype "bidirectional"))
      (node (ref "J3") (pin "SHLD3") (pinfunction "SHLD_SHLD3") (pintype "bidirectional"))
      (node (ref "J3") (pin "SHLD4") (pinfunction "SHLD_SHLD4") (pintype "bidirectional"))
      (node (ref "SHLD") (pin "2") (pinfunction "2_2") (pintype "passive"))
    )
    (net (code "45") (name "Net-(U2-PROG)") (class "Default")
      (node (ref "R3") (pin "2") (pinfunction "2_2") (pintype "passive"))
      (node (ref "U2") (pin "5") (pinfunction "PROG_5") (pintype "input"))
    )
    (net (code "46") (name "Net-(U2-STAT)") (class "Default")
      (node (ref "R5") (pin "1") (pinfunction "1_1") (pintype "passive"))
      (node (ref "U2") (pin "1") (pinfunction "STAT_1") (pintype "output"))
    )
    (net (code "47") (name "Net-(U5-EN)") (class "Default")
      (node (ref "D1") (pin "C") (pinfunction "C_C") (pintype "passive"))
      (node (ref "R9") (pin "1") (pinfunction "1_1") (pintype "passive"))
      (node (ref "U5") (pin "5") (pinfunction "EN_5") (pintype "bidirectional"))
      (node (ref "VE") (pin "2") (pinfunction "2_2") (pintype "passive"))
    )
    (net (code "48") (name "Net-(U5-IN)") (class "Default")
      (node (ref "5V_MEAS") (pin "2") (pinfunction "2_2") (pintype "passive"))
      (node (ref "5V_MEAS") (pin "4") (pinfunction "2_4") (pintype "passive"))
      (node (ref "C5") (pin "1") (pinfunction "1_1") (pintype "passive"))
      (node (ref "C8") (pin "1") (pinfunction "1_1") (pintype "passive"))
      (node (ref "R9") (pin "2") (pinfunction "2_2") (pintype "passive"))
      (node (ref "U5") (pin "8") (pinfunction "IN_8") (pintype "input"))
    )
    (net (code "49") (name "Net-(U5-OUT)") (class "Default")
      (node (ref "3V3_MEAS") (pin "1") (pinfunction "1_1") (pintype "passive"))
      (node (ref "3V3_MEAS") (pin "3") (pinfunction "1_3") (pintype "passive"))
      (node (ref "C11") (pin "1") (pinfunction "1_1") (pintype "passive"))
      (node (ref "C9") (pin "1") (pinfunction "1_1") (pintype "passive"))
      (node (ref "U5") (pin "1") (pinfunction "OUT_1") (pintype "output"))
    )
    (net (code "50") (name "PROCESSOR_CAN-RX") (class "Default")
      (node (ref "J1") (pin "41") (pinfunction "CAN-RX_41") (pintype "bidirectional"))
      (node (ref "J6") (pin "43") (pinfunction "CAN-TX_43") (pintype "bidirectional"))
    )
    (net (code "51") (name "PROCESSOR_CAN-TX") (class "Default")
      (node (ref "J1") (pin "43") (pinfunction "CAN-TX_43") (pintype "bidirectional"))
      (node (ref "J6") (pin "41") (pinfunction "CAN-RX_41") (pintype "bidirectional"))
    )
    (net (code "52") (name "PWM0-PROCESSOR") (class "Default")
      (node (ref "J1") (pin "32") (pinfunction "PWM0_32") (pintype "bidirectional"))
      (node (ref "J6") (pin "51") (pinfunction "F2/PWM_51") (pintype "bidirectional"))
    )
    (net (code "53") (name "PWM1-PROCESSOR") (class "Default")
      (node (ref "J1") (pin "47") (pinfunction "PWM1_47") (pintype "bidirectional"))
      (node (ref "J7") (pin "51") (pinfunction "F2/PWM_51") (pintype "bidirectional"))
    )
    (net (code "54") (name "RTS1-PROCESSOR") (class "Default")
      (node (ref "J1") (pin "13") (pinfunction "RTS1_13") (pintype "bidirectional"))
      (node (ref "J6") (pin "18") (pinfunction "CTS_18") (pintype "bidirectional"))
    )
    (net (code "55") (name "RX1-DFU_TX-FC0-PLEX") (class "Default")
      (node (ref "J6") (pin "4") (pinfunction "MCU_DFU_TX_4") (pintype "bidirectional"))
      (node (ref "U1") (pin "P9") (pinfunction "2S1_P9") (pintype "bidirectional"))
    )
    (net (code "56") (name "RX1-DFU_TX-FC1-PLEX") (class "Default")
      (node (ref "J7") (pin "4") (pinfunction "MCU_DFU_TX_4") (pintype "bidirectional"))
      (node (ref "U1") (pin "P8") (pinfunction "2S2_P8") (pintype "bidirectional"))
    )
    (net (code "57") (name "RX1-PROCESSOR") (class "Default")
      (node (ref "J1") (pin "19") (pinfunction "RX1_19") (pintype "bidirectional"))
      (node (ref "U1") (pin "P6") (pinfunction "D2_P6") (pintype "bidirectional"))
    )
    (net (code "58") (name "RX1-PROCESSOR-PLEX") (class "Default")
      (node (ref "J6") (pin "13") (pinfunction "TX_13") (pintype "bidirectional"))
      (node (ref "U1") (pin "P7") (pinfunction "2S3_P7") (pintype "bidirectional"))
    )
    (net (code "59") (name "RX2-PROCESSOR") (class "Default")
      (node (ref "J1") (pin "20") (pinfunction "RX2_20") (pintype "bidirectional"))
      (node (ref "J7") (pin "13") (pinfunction "TX_13") (pintype "bidirectional"))
    )
    (net (code "60") (name "SDIO_DATA1{slash}PWR_EN1_ALT") (class "Default")
      (node (ref "J1") (pin "66") (pinfunction "SDIO_DATA1_66") (pintype "bidirectional"))
      (node (ref "J7") (pin "71") (pinfunction "PWR_EN_71") (pintype "bidirectional"))
      (node (ref "S7") (pin "3") (pinfunction "S_3") (pintype "passive"))
    )
    (net (code "61") (name "SDIO_DATA2{slash}PWR_EN0_ALT") (class "Default")
      (node (ref "J1") (pin "68") (pinfunction "SDIO_DATA2_68") (pintype "bidirectional"))
      (node (ref "J6") (pin "71") (pinfunction "PWR_EN_71") (pintype "bidirectional"))
      (node (ref "S3") (pin "3") (pinfunction "S_3") (pintype "passive"))
    )
    (net (code "62") (name "SPI_PROCESSOR_SCK") (class "Default")
      (node (ref "J1") (pin "57") (pinfunction "SPI_SCK_57") (pintype "bidirectional"))
      (node (ref "J10") (pin "5") (pinfunction "CLK/SCK_5") (pintype "bidirectional"))
      (node (ref "J6") (pin "3") (pinfunction "SPI_SCK_3") (pintype "bidirectional"))
      (node (ref "J7") (pin "3") (pinfunction "SPI_SCK_3") (pintype "bidirectional"))
    )
    (net (code "63") (name "SPI_PROCESSOR_SDI") (class "Default")
      (node (ref "J1") (pin "61") (pinfunction "SPI_SDI_61") (pintype "bidirectional"))
      (node (ref "J10") (pin "7") (pinfunction "DAT0/SDO_7") (pintype "bidirectional"))
      (node (ref "J6") (pin "7") (pinfunction "SPI_SDO_7") (pintype "bidirectional"))
      (node (ref "J7") (pin "7") (pinfunction "SPI_SDO_7") (pintype "bidirectional"))
    )
    (net (code "64") (name "SPI_PROCESSOR_SDO") (class "Default")
      (node (ref "J1") (pin "59") (pinfunction "SPI_SDO_59") (pintype "bidirectional"))
      (node (ref "J10") (pin "3") (pinfunction "CMD/SDI_3") (pintype "bidirectional"))
      (node (ref "J6") (pin "5") (pinfunction "SPI_SDI_5") (pintype "bidirectional"))
      (node (ref "J7") (pin "5") (pinfunction "SPI_SDI_5") (pintype "bidirectional"))
    )
    (net (code "65") (name "SPI_SCK1-PROCESSOR") (class "Default")
      (node (ref "J1") (pin "60") (pinfunction "SPI_SCK1/SDIO_CLK_60") (pintype "bidirectional"))
      (node (ref "J7") (pin "61") (pinfunction "F7_61") (pintype "bidirectional"))
    )
    (net (code "66") (name "SPI_SDO1-PROCESSOR") (class "Default")
      (node (ref "J1") (pin "62") (pinfunction "SPI_SDO1/SDIO_CMD_62") (pintype "bidirectional"))
      (node (ref "J7") (pin "59") (pinfunction "F6_59") (pintype "bidirectional"))
    )
    (net (code "67") (name "SWDCK") (class "Default")
      (node (ref "J1") (pin "21") (pinfunction "SWDCK_21") (pintype "bidirectional"))
      (node (ref "J5") (pin "4") (pinfunction "SWDCLK_4") (pintype "bidirectional"))
    )
    (net (code "68") (name "SWDIO") (class "Default")
      (node (ref "J1") (pin "23") (pinfunction "SWDIO_23") (pintype "bidirectional"))
      (node (ref "J5") (pin "2") (pinfunction "SWDIO_2") (pintype "bidirectional"))
      (node (ref "TP1") (pin "1") (pinfunction "1_1") (pintype "bidirectional"))
    )
    (net (code "69") (name "TX1-DFU_RX-FC0-PLEX") (class "Default")
      (node (ref "J6") (pin "6") (pinfunction "MCU_DFU_RX_6") (pintype "bidirectional"))
      (node (ref "U1") (pin "P1") (pinfunction "1S1_P1") (pintype "bidirectional"))
    )
    (net (code "70") (name "TX1-DFU_RX-FC1-PLEX") (class "Default")
      (node (ref "J7") (pin "6") (pinfunction "MCU_DFU_RX_6") (pintype "bidirectional"))
      (node (ref "U1") (pin "P2") (pinfunction "1S2_P2") (pintype "bidirectional"))
    )
    (net (code "71") (name "TX1-PROCESSOR") (class "Default")
      (node (ref "J1") (pin "17") (pinfunction "TX1_17") (pintype "bidirectional"))
      (node (ref "U1") (pin "P4") (pinfunction "D1_P4") (pintype "bidirectional"))
    )
    (net (code "72") (name "TX1-PROCESSOR-PLEX") (class "Default")
      (node (ref "J6") (pin "15") (pinfunction "RX_15") (pintype "bidirectional"))
      (node (ref "U1") (pin "P3") (pinfunction "1S3_P3") (pintype "bidirectional"))
    )
    (net (code "73") (name "TX2-PROCESSOR") (class "Default")
      (node (ref "J1") (pin "22") (pinfunction "TX2_22") (pintype "bidirectional"))
      (node (ref "J7") (pin "15") (pinfunction "RX_15") (pintype "bidirectional"))
    )
    (net (code "74") (name "VCC") (class "Default")
      (node (ref "5V_MEAS") (pin "1") (pinfunction "1_1") (pintype "passive"))
      (node (ref "5V_MEAS") (pin "3") (pinfunction "1_3") (pintype "passive"))
      (node (ref "C2") (pin "1") (pinfunction "1_1") (pintype "passive"))
      (node (ref "C3") (pin "1") (pinfunction "1_1") (pintype "passive"))
      (node (ref "D4") (pin "A") (pinfunction "A_A") (pintype "passive"))
      (node (ref "D5") (pin "C") (pinfunction "C_C") (pintype "passive"))
      (node (ref "J6") (pin "72") (pinfunction "VCC_72") (pintype "bidirectional"))
      (node (ref "J6") (pin "74") (pinfunction "VCC_74") (pintype "bidirectional"))
      (node (ref "J7") (pin "72") (pinfunction "VCC_72") (pintype "bidirectional"))
      (node (ref "J7") (pin "74") (pinfunction "VCC_74") (pintype "bidirectional"))
      (node (ref "Q1") (pin "2") (pinfunction "S_2") (pintype "bidirectional"))
      (node (ref "R4") (pin "2") (pinfunction "2_2") (pintype "passive"))
      (node (ref "U2") (pin "4") (pinfunction "VIN_4") (pintype "power_in"))
      (node (ref "U4") (pin "1") (pinfunction "IN_1") (pintype "input"))
    )
    (net (code "75") (name "VIN") (class "Default")
      (node (ref "BYP") (pin "2") (pinfunction "2_2") (pintype "passive"))
      (node (ref "D5") (pin "A") (pinfunction "A_A") (pintype "passive"))
      (node (ref "F2") (pin "2") (pinfunction "2_2") (pintype "bidirectional"))
      (node (ref "J1") (pin "9") (pinfunction "USB_VIN_9") (pintype "bidirectional"))
      (node (ref "Q1") (pin "1") (pinfunction "G_1") (pintype "bidirectional"))
      (node (ref "R10") (pin "2") (pinfunction "2_2") (pintype "passive"))
      (node (ref "R6") (pin "2") (pinfunction "2_2") (pintype "passive"))
      (node (ref "R8") (pin "2") (pinfunction "2_2") (pintype "passive"))
      (node (ref "TP4") (pin "1") (pinfunction "1_1") (pintype "bidirectional"))
    )
    (net (code "76") (name "VIN{slash}3") (class "Default")
      (node (ref "J1") (pin "49") (pinfunction "BATT_VIN/3_49") (pintype "bidirectional"))
      (node (ref "R10") (pin "1") (pinfunction "1_1") (pintype "passive"))
      (node (ref "R7") (pin "2") (pinfunction "2_2") (pintype "passive"))
    )
    (net (code "77") (name "V_BATT") (class "Default")
      (node (ref "C4") (pin "1") (pinfunction "1_1") (pintype "passive"))
      (node (ref "J8") (pin "2") (pinfunction "+_2") (pintype "bidirectional"))
      (node (ref "Q1") (pin "3") (pinfunction "D_3") (pintype "bidirectional"))
      (node (ref "TP3") (pin "1") (pinfunction "1_1") (pintype "bidirectional"))
      (node (ref "U2") (pin "3") (pinfunction "VBAT_3") (pintype "power_in"))
    )
    (net (code "78") (name "V_USB") (class "Default")
      (node (ref "BYP") (pin "1") (pinfunction "1_1") (pintype "passive"))
      (node (ref "F2") (pin "1") (pinfunction "1_1") (pintype "bidirectional"))
      (node (ref "J3") (pin "VBUS1") (pinfunction "VBUS_VBUS1") (pintype "bidirectional"))
      (node (ref "J3") (pin "VBUS2") (pinfunction "VBUS_VBUS2") (pintype "bidirectional"))
      (node (ref "U3") (pin "5") (pinfunction "VCC_5") (pintype "bidirectional"))
    )
    (net (code "79") (name "unconnected-(J1-AUD_BCLK-Pad50)") (class "Default")
      (node (ref "J1") (pin "50") (pinfunction "AUD_BCLK_50") (pintype "bidirectional"))
    )
    (net (code "80") (name "unconnected-(J1-AUD_IN{slash}CAM_PCLK-Pad54)") (class "Default")
      (node (ref "J1") (pin "54") (pinfunction "AUD_IN/CAM_PCLK_54") (pintype "bidirectional"))
    )
    (net (code "81") (name "unconnected-(J1-AUD_LRCLK-Pad52)") (class "Default")
      (node (ref "J1") (pin "52") (pinfunction "AUD_LRCLK_52") (pintype "bidirectional"))
    )
    (net (code "82") (name "unconnected-(J1-AUD_MCLK-Pad58)") (class "Default")
      (node (ref "J1") (pin "58") (pinfunction "AUD_MCLK_58") (pintype "bidirectional"))
    )
    (net (code "83") (name "unconnected-(J1-AUD_OUT{slash}CAM_MCLK-Pad56)") (class "Default")
      (node (ref "J1") (pin "56") (pinfunction "AUD_OUT/CAM_MCLK_56") (pintype "bidirectional"))
    )
    (net (code "84") (name "unconnected-(J1-G8-Pad67)") (class "Default")
      (node (ref "J1") (pin "67") (pinfunction "G8_67") (pintype "bidirectional"))
    )
    (net (code "85") (name "unconnected-(J1-G9{slash}ADC_D-{slash}CAM_HSYNC-Pad65)") (class "Default")
      (node (ref "J1") (pin "65") (pinfunction "G9/ADC_D-/CAM_HSYNC_65") (pintype "bidirectional"))
    )
    (net (code "86") (name "unconnected-(J1-G10{slash}ADC_D+{slash}CAM_VSYNC-Pad63)") (class "Default")
      (node (ref "J1") (pin "63") (pinfunction "G10/ADC_D+/CAM_VSYNC_63") (pintype "bidirectional"))
    )
    (net (code "87") (name "unconnected-(J1-G11-Pad8)") (class "Default")
      (node (ref "J1") (pin "8") (pinfunction "G11_8") (pintype "bidirectional"))
    )
    (net (code "88") (name "unconnected-(J1-I2C_SDA1-Pad51)") (class "Default")
      (node (ref "J1") (pin "51") (pinfunction "I2C_SDA1_51") (pintype "bidirectional"))
    )
    (net (code "89") (name "unconnected-(J1-RTC_3V-Pad72)") (class "Default")
      (node (ref "J1") (pin "72") (pinfunction "RTC_3V_72") (pintype "bidirectional"))
    )
    (net (code "90") (name "unconnected-(J1-SPI_SDI1{slash}SDIO_DATA0-Pad64)") (class "Default")
      (node (ref "J1") (pin "64") (pinfunction "SPI_SDI1/SDIO_DATA0_64") (pintype "bidirectional"))
    )
    (net (code "91") (name "unconnected-(J5-SWO-Pad6)") (class "Default")
      (node (ref "J5") (pin "6") (pinfunction "SWO_6") (pintype "bidirectional"))
    )
    (net (code "92") (name "unconnected-(J6-EEPROM_WP-Pad40)") (class "Default")
      (node (ref "J6") (pin "40") (pinfunction "EEPROM_WP_40") (pintype "bidirectional"))
    )
    (net (code "93") (name "unconnected-(J6-USB_VIN-Pad70)") (class "Default")
      (node (ref "J6") (pin "70") (pinfunction "USB_VIN_70") (pintype "bidirectional"))
    )
    (net (code "94") (name "unconnected-(J7-CAN-RX-Pad41)") (class "Default")
      (node (ref "J7") (pin "41") (pinfunction "CAN-RX_41") (pintype "bidirectional"))
    )
    (net (code "95") (name "unconnected-(J7-CAN-TX-Pad43)") (class "Default")
      (node (ref "J7") (pin "43") (pinfunction "CAN-TX_43") (pintype "bidirectional"))
    )
    (net (code "96") (name "unconnected-(J7-CTS-Pad18)") (class "Default")
      (node (ref "J7") (pin "18") (pinfunction "CTS_18") (pintype "bidirectional"))
    )
    (net (code "97") (name "unconnected-(J7-EEPROM_WP-Pad40)") (class "Default")
      (node (ref "J7") (pin "40") (pinfunction "EEPROM_WP_40") (pintype "bidirectional"))
    )
    (net (code "98") (name "unconnected-(J7-RTS-Pad16)") (class "Default")
      (node (ref "J7") (pin "16") (pinfunction "RTS_16") (pintype "bidirectional"))
    )
    (net (code "99") (name "unconnected-(J7-USBHOST_D+-Pad35)") (class "Default")
      (node (ref "J7") (pin "35") (pinfunction "USBHOST_D+_35") (pintype "bidirectional"))
    )
    (net (code "100") (name "unconnected-(J7-USBHOST_D--Pad37)") (class "Default")
      (node (ref "J7") (pin "37") (pinfunction "USBHOST_D-_37") (pintype "bidirectional"))
    )
    (net (code "101") (name "unconnected-(J7-USB_VIN-Pad70)") (class "Default")
      (node (ref "J7") (pin "70") (pinfunction "USB_VIN_70") (pintype "bidirectional"))
    )
    (net (code "102") (name "unconnected-(J8-PAD1-PadNC1)") (class "Default")
      (node (ref "J8") (pin "NC1") (pinfunction "PAD1_NC1") (pintype "bidirectional"))
    )
    (net (code "103") (name "unconnected-(J8-PAD2-PadNC2)") (class "Default")
      (node (ref "J8") (pin "NC2") (pinfunction "PAD2_NC2") (pintype "bidirectional"))
    )
    (net (code "104") (name "unconnected-(J10-DAT1-Pad8)") (class "Default")
      (node (ref "J10") (pin "8") (pinfunction "DAT1_8") (pintype "bidirectional"))
    )
    (net (code "105") (name "unconnected-(J10-DAT2-Pad1)") (class "Default")
      (node (ref "J10") (pin "1") (pinfunction "DAT2_1") (pintype "bidirectional"))
    )
    (net (code "106") (name "unconnected-(J10-DET-Pad9)") (class "Default")
      (node (ref "J10") (pin "9") (pinfunction "DET_9") (pintype "bidirectional"))
    )
    (net (code "107") (name "unconnected-(U3-IO3-Pad4)") (class "Default")
      (node (ref "U3") (pin "4") (pinfunction "IO3_4") (pintype "bidirectional"))
    )
    (net (code "108") (name "unconnected-(U3-IO4-Pad6)") (class "Default")
      (node (ref "U3") (pin "6") (pinfunction "IO4_6") (pintype "bidirectional"))
    )
  )
)
